# untitled.net
KiCad netlist of a schematic drawn in EAGLE
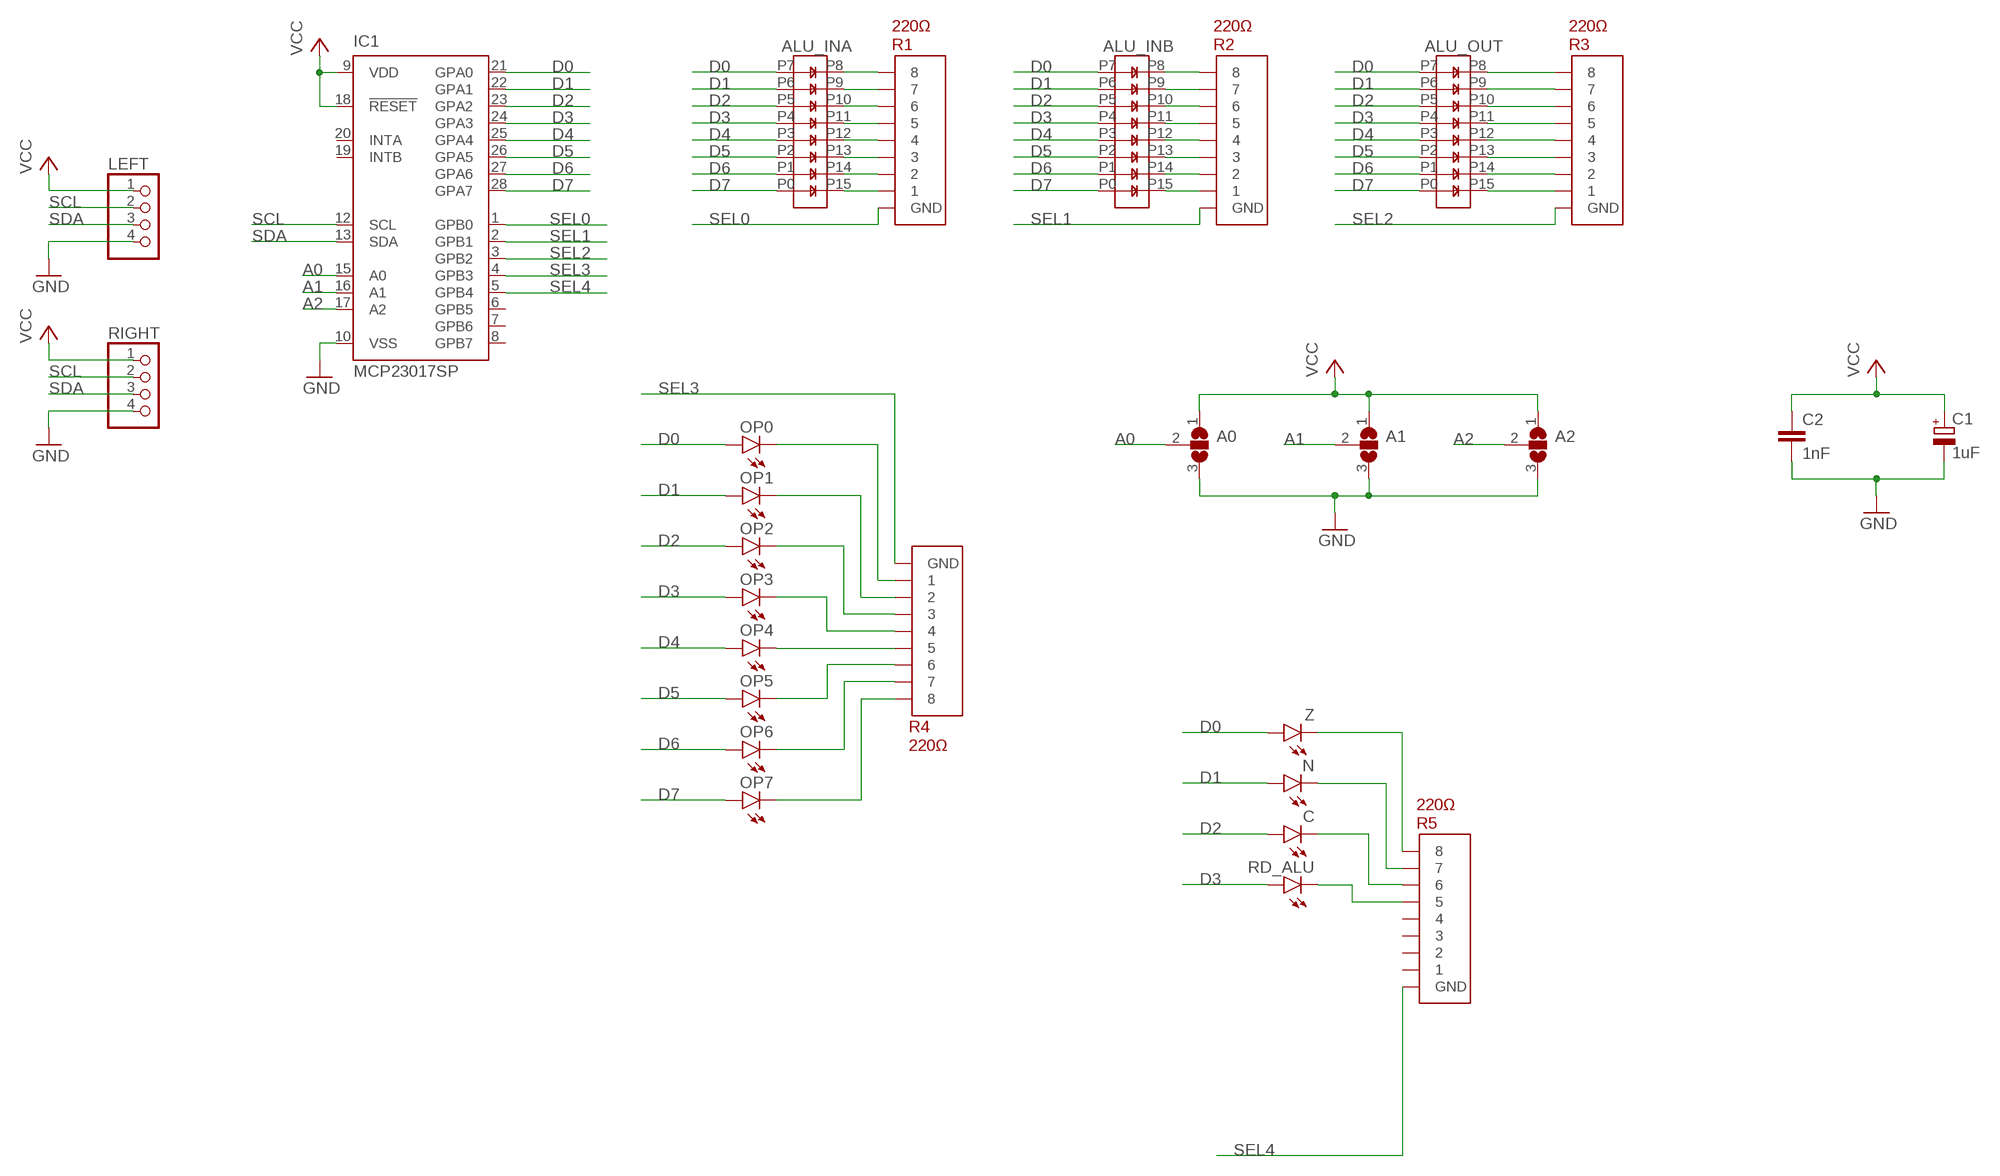
[diagram p0: schematic, sheet 1]

(export (version "E")
  (design (tool "Eeschema 10.0.6"))
  (components
    (comp (ref "A0")
      (value "SJ2W")
      (footprint "eagle-import:SJ_2")
      (libsource (lib "eagle-import") (part "SJ2W"))
    )
    (comp (ref "A1")
      (value "SJ2W")
      (footprint "eagle-import:SJ_2")
      (libsource (lib "eagle-import") (part "SJ2W"))
    )
    (comp (ref "A2")
      (value "SJ2W")
      (footprint "eagle-import:SJ_2")
      (libsource (lib "eagle-import") (part "SJ2W"))
    )
    (comp (ref "ALU_INA")
      (value "LB8")
      (footprint "eagle-import:LB8")
      (libsource (lib "eagle-import") (part "LB8"))
    )
    (comp (ref "ALU_INB")
      (value "LB8")
      (footprint "eagle-import:LB8")
      (libsource (lib "eagle-import") (part "LB8"))
    )
    (comp (ref "ALU_OUT")
      (value "LB8")
      (footprint "eagle-import:LB8")
      (libsource (lib "eagle-import") (part "LB8"))
    )
    (comp (ref "C")
      (value "LED3MM")
      (footprint "eagle-import:LED3MM")
      (libsource (lib "eagle-import") (part "LED3MM"))
    )
    (comp (ref "C1")
      (value "1uF")
      (footprint "eagle-import:E2,5-6")
      (libsource (lib "eagle-import") (part "CPOL-EUE2.5-6"))
    )
    (comp (ref "C2")
      (value "1nF")
      (footprint "eagle-import:C2.5-2")
      (libsource (lib "eagle-import") (part "C2.5/2"))
    )
    (comp (ref "IC1")
      (value "MCP23017SP")
      (footprint "eagle-import:DIL28-3")
      (fields (field (name "MF") "MICROCHIP") (field (name "MPN") "MCP23017-E/SP"))
      (libsource (lib "eagle-import") (part "MCP23017SP"))
    )
    (comp (ref "LEFT")
      (value "PINHD-1X4")
      (footprint "eagle-import:1X04")
      (libsource (lib "eagle-import") (part "PINHD-1X4"))
    )
    (comp (ref "N")
      (value "LED3MM")
      (footprint "eagle-import:LED3MM")
      (libsource (lib "eagle-import") (part "LED3MM"))
    )
    (comp (ref "OP0")
      (value "LED3MM")
      (footprint "eagle-import:LED3MM")
      (libsource (lib "eagle-import") (part "LED3MM"))
    )
    (comp (ref "OP1")
      (value "LED3MM")
      (footprint "eagle-import:LED3MM")
      (libsource (lib "eagle-import") (part "LED3MM"))
    )
    (comp (ref "OP2")
      (value "LED3MM")
      (footprint "eagle-import:LED3MM")
      (libsource (lib "eagle-import") (part "LED3MM"))
    )
    (comp (ref "OP3")
      (value "LED3MM")
      (footprint "eagle-import:LED3MM")
      (libsource (lib "eagle-import") (part "LED3MM"))
    )
    (comp (ref "OP4")
      (value "LED3MM")
      (footprint "eagle-import:LED3MM")
      (libsource (lib "eagle-import") (part "LED3MM"))
    )
    (comp (ref "OP5")
      (value "LED3MM")
      (footprint "eagle-import:LED3MM")
      (libsource (lib "eagle-import") (part "LED3MM"))
    )
    (comp (ref "OP6")
      (value "LED3MM")
      (footprint "eagle-import:LED3MM")
      (libsource (lib "eagle-import") (part "LED3MM"))
    )
    (comp (ref "OP7")
      (value "LED3MM")
      (footprint "eagle-import:LED3MM")
      (libsource (lib "eagle-import") (part "LED3MM"))
    )
    (comp (ref "R1")
      (value "220Ω")
      (footprint "eagle-import:R_ARRAY_8PIN")
      (libsource (lib "eagle-import") (part "R_ARRAY_8PIN"))
    )
    (comp (ref "R2")
      (value "220Ω")
      (footprint "eagle-import:R_ARRAY_8PIN")
      (libsource (lib "eagle-import") (part "R_ARRAY_8PIN"))
    )
    (comp (ref "R3")
      (value "220Ω")
      (footprint "eagle-import:R_ARRAY_8PIN")
      (libsource (lib "eagle-import") (part "R_ARRAY_8PIN"))
    )
    (comp (ref "R4")
      (value "220Ω")
      (footprint "eagle-import:R_ARRAY_8PIN")
      (libsource (lib "eagle-import") (part "R_ARRAY_8PIN"))
    )
    (comp (ref "R5")
      (value "220Ω")
      (footprint "eagle-import:R_ARRAY_8PIN")
      (libsource (lib "eagle-import") (part "R_ARRAY_8PIN"))
    )
    (comp (ref "RD_ALU")
      (value "LED3MM")
      (footprint "eagle-import:LED3MM")
      (libsource (lib "eagle-import") (part "LED3MM"))
    )
    (comp (ref "RIGHT")
      (value "PINHD-1X4")
      (footprint "eagle-import:1X04")
      (libsource (lib "eagle-import") (part "PINHD-1X4"))
    )
    (comp (ref "Z")
      (value "LED3MM")
      (footprint "eagle-import:LED3MM")
      (libsource (lib "eagle-import") (part "LED3MM"))
    )
  )
  (nets
    (net (code "1") (name "/A0") (class "Default")
      (node (ref "A0") (pin "2") (pinfunction "2_2") (pintype "passive"))
      (node (ref "IC1") (pin "15") (pinfunction "A0_15") (pintype "input"))
    )
    (net (code "2") (name "/A1") (class "Default")
      (node (ref "A1") (pin "2") (pinfunction "2_2") (pintype "passive"))
      (node (ref "IC1") (pin "16") (pinfunction "A1_16") (pintype "input"))
    )
    (net (code "3") (name "/A2") (class "Default")
      (node (ref "A2") (pin "2") (pinfunction "2_2") (pintype "passive"))
      (node (ref "IC1") (pin "17") (pinfunction "A2_17") (pintype "input"))
    )
    (net (code "4") (name "/D0") (class "Default")
      (node (ref "ALU_INA") (pin "P7") (pinfunction "P7_P7") (pintype "bidirectional"))
      (node (ref "ALU_INB") (pin "P7") (pinfunction "P7_P7") (pintype "bidirectional"))
      (node (ref "ALU_OUT") (pin "P7") (pinfunction "P7_P7") (pintype "bidirectional"))
      (node (ref "IC1") (pin "21") (pinfunction "GPA0_21") (pintype "bidirectional"))
      (node (ref "OP0") (pin "A") (pinfunction "A_A") (pintype "passive"))
      (node (ref "Z") (pin "A") (pinfunction "A_A") (pintype "passive"))
    )
    (net (code "5") (name "/D1") (class "Default")
      (node (ref "ALU_INA") (pin "P6") (pinfunction "P6_P6") (pintype "bidirectional"))
      (node (ref "ALU_INB") (pin "P6") (pinfunction "P6_P6") (pintype "bidirectional"))
      (node (ref "ALU_OUT") (pin "P6") (pinfunction "P6_P6") (pintype "bidirectional"))
      (node (ref "IC1") (pin "22") (pinfunction "GPA1_22") (pintype "bidirectional"))
      (node (ref "N") (pin "A") (pinfunction "A_A") (pintype "passive"))
      (node (ref "OP1") (pin "A") (pinfunction "A_A") (pintype "passive"))
    )
    (net (code "6") (name "/D2") (class "Default")
      (node (ref "ALU_INA") (pin "P5") (pinfunction "P5_P5") (pintype "bidirectional"))
      (node (ref "ALU_INB") (pin "P5") (pinfunction "P5_P5") (pintype "bidirectional"))
      (node (ref "ALU_OUT") (pin "P5") (pinfunction "P5_P5") (pintype "bidirectional"))
      (node (ref "C") (pin "A") (pinfunction "A_A") (pintype "passive"))
      (node (ref "IC1") (pin "23") (pinfunction "GPA2_23") (pintype "bidirectional"))
      (node (ref "OP2") (pin "A") (pinfunction "A_A") (pintype "passive"))
    )
    (net (code "7") (name "/D3") (class "Default")
      (node (ref "ALU_INA") (pin "P4") (pinfunction "P4_P4") (pintype "bidirectional"))
      (node (ref "ALU_INB") (pin "P4") (pinfunction "P4_P4") (pintype "bidirectional"))
      (node (ref "ALU_OUT") (pin "P4") (pinfunction "P4_P4") (pintype "bidirectional"))
      (node (ref "IC1") (pin "24") (pinfunction "GPA3_24") (pintype "bidirectional"))
      (node (ref "OP3") (pin "A") (pinfunction "A_A") (pintype "passive"))
      (node (ref "RD_ALU") (pin "A") (pinfunction "A_A") (pintype "passive"))
    )
    (net (code "8") (name "/D4") (class "Default")
      (node (ref "ALU_INA") (pin "P3") (pinfunction "P3_P3") (pintype "bidirectional"))
      (node (ref "ALU_INB") (pin "P3") (pinfunction "P3_P3") (pintype "bidirectional"))
      (node (ref "ALU_OUT") (pin "P3") (pinfunction "P3_P3") (pintype "bidirectional"))
      (node (ref "IC1") (pin "25") (pinfunction "GPA4_25") (pintype "bidirectional"))
      (node (ref "OP4") (pin "A") (pinfunction "A_A") (pintype "passive"))
    )
    (net (code "9") (name "/D5") (class "Default")
      (node (ref "ALU_INA") (pin "P2") (pinfunction "P2_P2") (pintype "bidirectional"))
      (node (ref "ALU_INB") (pin "P2") (pinfunction "P2_P2") (pintype "bidirectional"))
      (node (ref "ALU_OUT") (pin "P2") (pinfunction "P2_P2") (pintype "bidirectional"))
      (node (ref "IC1") (pin "26") (pinfunction "GPA5_26") (pintype "bidirectional"))
      (node (ref "OP5") (pin "A") (pinfunction "A_A") (pintype "passive"))
    )
    (net (code "10") (name "/D6") (class "Default")
      (node (ref "ALU_INA") (pin "P1") (pinfunction "P1_P1") (pintype "bidirectional"))
      (node (ref "ALU_INB") (pin "P1") (pinfunction "P1_P1") (pintype "bidirectional"))
      (node (ref "ALU_OUT") (pin "P1") (pinfunction "P1_P1") (pintype "bidirectional"))
      (node (ref "IC1") (pin "27") (pinfunction "GPA6_27") (pintype "bidirectional"))
      (node (ref "OP6") (pin "A") (pinfunction "A_A") (pintype "passive"))
    )
    (net (code "11") (name "/D7") (class "Default")
      (node (ref "ALU_INA") (pin "P0") (pinfunction "P0_P0") (pintype "bidirectional"))
      (node (ref "ALU_INB") (pin "P0") (pinfunction "P0_P0") (pintype "bidirectional"))
      (node (ref "ALU_OUT") (pin "P0") (pinfunction "P0_P0") (pintype "bidirectional"))
      (node (ref "IC1") (pin "28") (pinfunction "GPA7_28") (pintype "bidirectional"))
      (node (ref "OP7") (pin "A") (pinfunction "A_A") (pintype "passive"))
    )
    (net (code "12") (name "/SCL") (class "Default")
      (node (ref "IC1") (pin "12") (pinfunction "SCL_12") (pintype "input"))
      (node (ref "LEFT") (pin "2") (pinfunction "2_2") (pintype "passive"))
      (node (ref "RIGHT") (pin "2") (pinfunction "2_2") (pintype "passive"))
    )
    (net (code "13") (name "/SDA") (class "Default")
      (node (ref "IC1") (pin "13") (pinfunction "SDA_13") (pintype "bidirectional"))
      (node (ref "LEFT") (pin "3") (pinfunction "3_3") (pintype "passive"))
      (node (ref "RIGHT") (pin "3") (pinfunction "3_3") (pintype "passive"))
    )
    (net (code "14") (name "/SEL0") (class "Default")
      (node (ref "IC1") (pin "1") (pinfunction "GPB0_1") (pintype "bidirectional"))
      (node (ref "R1") (pin "GND") (pinfunction "GND_GND") (pintype "bidirectional"))
    )
    (net (code "15") (name "/SEL1") (class "Default")
      (node (ref "IC1") (pin "2") (pinfunction "GPB1_2") (pintype "bidirectional"))
      (node (ref "R2") (pin "GND") (pinfunction "GND_GND") (pintype "bidirectional"))
    )
    (net (code "16") (name "/SEL2") (class "Default")
      (node (ref "IC1") (pin "3") (pinfunction "GPB2_3") (pintype "bidirectional"))
      (node (ref "R3") (pin "GND") (pinfunction "GND_GND") (pintype "bidirectional"))
    )
    (net (code "17") (name "/SEL3") (class "Default")
      (node (ref "IC1") (pin "4") (pinfunction "GPB3_4") (pintype "bidirectional"))
      (node (ref "R4") (pin "GND") (pinfunction "GND_GND") (pintype "bidirectional"))
    )
    (net (code "18") (name "/SEL4") (class "Default")
      (node (ref "IC1") (pin "5") (pinfunction "GPB4_5") (pintype "bidirectional"))
      (node (ref "R5") (pin "GND") (pinfunction "GND_GND") (pintype "bidirectional"))
    )
    (net (code "19") (name "GND") (class "Default")
      (node (ref "A0") (pin "3") (pinfunction "3_3") (pintype "passive"))
      (node (ref "A1") (pin "3") (pinfunction "3_3") (pintype "passive"))
      (node (ref "A2") (pin "3") (pinfunction "3_3") (pintype "passive"))
      (node (ref "C1") (pin "-") (pinfunction "-_-") (pintype "passive"))
      (node (ref "C2") (pin "2") (pinfunction "2_2") (pintype "passive"))
      (node (ref "IC1") (pin "10") (pinfunction "VSS_10") (pintype "power_in"))
      (node (ref "LEFT") (pin "4") (pinfunction "4_4") (pintype "passive"))
      (node (ref "RIGHT") (pin "4") (pinfunction "4_4") (pintype "passive"))
    )
    (net (code "20") (name "Net-(ALU_INA-PadP8)") (class "Default")
      (node (ref "ALU_INA") (pin "P8") (pinfunction "P8_P8") (pintype "bidirectional"))
      (node (ref "R1") (pin "8") (pinfunction "8_8") (pintype "bidirectional"))
    )
    (net (code "21") (name "Net-(ALU_INA-PadP9)") (class "Default")
      (node (ref "ALU_INA") (pin "P9") (pinfunction "P9_P9") (pintype "bidirectional"))
      (node (ref "R1") (pin "7") (pinfunction "7_7") (pintype "bidirectional"))
    )
    (net (code "22") (name "Net-(ALU_INA-PadP10)") (class "Default")
      (node (ref "ALU_INA") (pin "P10") (pinfunction "P10_P10") (pintype "bidirectional"))
      (node (ref "R1") (pin "6") (pinfunction "6_6") (pintype "bidirectional"))
    )
    (net (code "23") (name "Net-(ALU_INA-PadP11)") (class "Default")
      (node (ref "ALU_INA") (pin "P11") (pinfunction "P11_P11") (pintype "bidirectional"))
      (node (ref "R1") (pin "5") (pinfunction "5_5") (pintype "bidirectional"))
    )
    (net (code "24") (name "Net-(ALU_INA-PadP12)") (class "Default")
      (node (ref "ALU_INA") (pin "P12") (pinfunction "P12_P12") (pintype "bidirectional"))
      (node (ref "R1") (pin "4") (pinfunction "4_4") (pintype "bidirectional"))
    )
    (net (code "25") (name "Net-(ALU_INA-PadP13)") (class "Default")
      (node (ref "ALU_INA") (pin "P13") (pinfunction "P13_P13") (pintype "bidirectional"))
      (node (ref "R1") (pin "3") (pinfunction "3_3") (pintype "bidirectional"))
    )
    (net (code "26") (name "Net-(ALU_INA-PadP14)") (class "Default")
      (node (ref "ALU_INA") (pin "P14") (pinfunction "P14_P14") (pintype "bidirectional"))
      (node (ref "R1") (pin "2") (pinfunction "2_2") (pintype "bidirectional"))
    )
    (net (code "27") (name "Net-(ALU_INA-PadP15)") (class "Default")
      (node (ref "ALU_INA") (pin "P15") (pinfunction "P15_P15") (pintype "bidirectional"))
      (node (ref "R1") (pin "1") (pinfunction "1_1") (pintype "bidirectional"))
    )
    (net (code "28") (name "Net-(ALU_INB-PadP8)") (class "Default")
      (node (ref "ALU_INB") (pin "P8") (pinfunction "P8_P8") (pintype "bidirectional"))
      (node (ref "R2") (pin "8") (pinfunction "8_8") (pintype "bidirectional"))
    )
    (net (code "29") (name "Net-(ALU_INB-PadP9)") (class "Default")
      (node (ref "ALU_INB") (pin "P9") (pinfunction "P9_P9") (pintype "bidirectional"))
      (node (ref "R2") (pin "7") (pinfunction "7_7") (pintype "bidirectional"))
    )
    (net (code "30") (name "Net-(ALU_INB-PadP10)") (class "Default")
      (node (ref "ALU_INB") (pin "P10") (pinfunction "P10_P10") (pintype "bidirectional"))
      (node (ref "R2") (pin "6") (pinfunction "6_6") (pintype "bidirectional"))
    )
    (net (code "31") (name "Net-(ALU_INB-PadP11)") (class "Default")
      (node (ref "ALU_INB") (pin "P11") (pinfunction "P11_P11") (pintype "bidirectional"))
      (node (ref "R2") (pin "5") (pinfunction "5_5") (pintype "bidirectional"))
    )
    (net (code "32") (name "Net-(ALU_INB-PadP12)") (class "Default")
      (node (ref "ALU_INB") (pin "P12") (pinfunction "P12_P12") (pintype "bidirectional"))
      (node (ref "R2") (pin "4") (pinfunction "4_4") (pintype "bidirectional"))
    )
    (net (code "33") (name "Net-(ALU_INB-PadP13)") (class "Default")
      (node (ref "ALU_INB") (pin "P13") (pinfunction "P13_P13") (pintype "bidirectional"))
      (node (ref "R2") (pin "3") (pinfunction "3_3") (pintype "bidirectional"))
    )
    (net (code "34") (name "Net-(ALU_INB-PadP14)") (class "Default")
      (node (ref "ALU_INB") (pin "P14") (pinfunction "P14_P14") (pintype "bidirectional"))
      (node (ref "R2") (pin "2") (pinfunction "2_2") (pintype "bidirectional"))
    )
    (net (code "35") (name "Net-(ALU_INB-PadP15)") (class "Default")
      (node (ref "ALU_INB") (pin "P15") (pinfunction "P15_P15") (pintype "bidirectional"))
      (node (ref "R2") (pin "1") (pinfunction "1_1") (pintype "bidirectional"))
    )
    (net (code "36") (name "Net-(ALU_OUT-PadP8)") (class "Default")
      (node (ref "ALU_OUT") (pin "P8") (pinfunction "P8_P8") (pintype "bidirectional"))
      (node (ref "R3") (pin "8") (pinfunction "8_8") (pintype "bidirectional"))
    )
    (net (code "37") (name "Net-(ALU_OUT-PadP9)") (class "Default")
      (node (ref "ALU_OUT") (pin "P9") (pinfunction "P9_P9") (pintype "bidirectional"))
      (node (ref "R3") (pin "7") (pinfunction "7_7") (pintype "bidirectional"))
    )
    (net (code "38") (name "Net-(ALU_OUT-PadP10)") (class "Default")
      (node (ref "ALU_OUT") (pin "P10") (pinfunction "P10_P10") (pintype "bidirectional"))
      (node (ref "R3") (pin "6") (pinfunction "6_6") (pintype "bidirectional"))
    )
    (net (code "39") (name "Net-(ALU_OUT-PadP11)") (class "Default")
      (node (ref "ALU_OUT") (pin "P11") (pinfunction "P11_P11") (pintype "bidirectional"))
      (node (ref "R3") (pin "5") (pinfunction "5_5") (pintype "bidirectional"))
    )
    (net (code "40") (name "Net-(ALU_OUT-PadP12)") (class "Default")
      (node (ref "ALU_OUT") (pin "P12") (pinfunction "P12_P12") (pintype "bidirectional"))
      (node (ref "R3") (pin "4") (pinfunction "4_4") (pintype "bidirectional"))
    )
    (net (code "41") (name "Net-(ALU_OUT-PadP13)") (class "Default")
      (node (ref "ALU_OUT") (pin "P13") (pinfunction "P13_P13") (pintype "bidirectional"))
      (node (ref "R3") (pin "3") (pinfunction "3_3") (pintype "bidirectional"))
    )
    (net (code "42") (name "Net-(ALU_OUT-PadP14)") (class "Default")
      (node (ref "ALU_OUT") (pin "P14") (pinfunction "P14_P14") (pintype "bidirectional"))
      (node (ref "R3") (pin "2") (pinfunction "2_2") (pintype "bidirectional"))
    )
    (net (code "43") (name "Net-(ALU_OUT-PadP15)") (class "Default")
      (node (ref "ALU_OUT") (pin "P15") (pinfunction "P15_P15") (pintype "bidirectional"))
      (node (ref "R3") (pin "1") (pinfunction "1_1") (pintype "bidirectional"))
    )
    (net (code "44") (name "Net-(C-C)") (class "Default")
      (node (ref "C") (pin "K") (pinfunction "C_K") (pintype "passive"))
      (node (ref "R5") (pin "6") (pinfunction "6_6") (pintype "bidirectional"))
    )
    (net (code "45") (name "Net-(N-C)") (class "Default")
      (node (ref "N") (pin "K") (pinfunction "C_K") (pintype "passive"))
      (node (ref "R5") (pin "7") (pinfunction "7_7") (pintype "bidirectional"))
    )
    (net (code "46") (name "Net-(OP0-C)") (class "Default")
      (node (ref "OP0") (pin "K") (pinfunction "C_K") (pintype "passive"))
      (node (ref "R4") (pin "1") (pinfunction "1_1") (pintype "bidirectional"))
    )
    (net (code "47") (name "Net-(OP1-C)") (class "Default")
      (node (ref "OP1") (pin "K") (pinfunction "C_K") (pintype "passive"))
      (node (ref "R4") (pin "2") (pinfunction "2_2") (pintype "bidirectional"))
    )
    (net (code "48") (name "Net-(OP2-C)") (class "Default")
      (node (ref "OP2") (pin "K") (pinfunction "C_K") (pintype "passive"))
      (node (ref "R4") (pin "3") (pinfunction "3_3") (pintype "bidirectional"))
    )
    (net (code "49") (name "Net-(OP3-C)") (class "Default")
      (node (ref "OP3") (pin "K") (pinfunction "C_K") (pintype "passive"))
      (node (ref "R4") (pin "4") (pinfunction "4_4") (pintype "bidirectional"))
    )
    (net (code "50") (name "Net-(OP4-C)") (class "Default")
      (node (ref "OP4") (pin "K") (pinfunction "C_K") (pintype "passive"))
      (node (ref "R4") (pin "5") (pinfunction "5_5") (pintype "bidirectional"))
    )
    (net (code "51") (name "Net-(OP5-C)") (class "Default")
      (node (ref "OP5") (pin "K") (pinfunction "C_K") (pintype "passive"))
      (node (ref "R4") (pin "6") (pinfunction "6_6") (pintype "bidirectional"))
    )
    (net (code "52") (name "Net-(OP6-C)") (class "Default")
      (node (ref "OP6") (pin "K") (pinfunction "C_K") (pintype "passive"))
      (node (ref "R4") (pin "7") (pinfunction "7_7") (pintype "bidirectional"))
    )
    (net (code "53") (name "Net-(OP7-C)") (class "Default")
      (node (ref "OP7") (pin "K") (pinfunction "C_K") (pintype "passive"))
      (node (ref "R4") (pin "8") (pinfunction "8_8") (pintype "bidirectional"))
    )
    (net (code "54") (name "Net-(RD_ALU-C)") (class "Default")
      (node (ref "R5") (pin "5") (pinfunction "5_5") (pintype "bidirectional"))
      (node (ref "RD_ALU") (pin "K") (pinfunction "C_K") (pintype "passive"))
    )
    (net (code "55") (name "Net-(Z-C)") (class "Default")
      (node (ref "R5") (pin "8") (pinfunction "8_8") (pintype "bidirectional"))
      (node (ref "Z") (pin "K") (pinfunction "C_K") (pintype "passive"))
    )
    (net (code "56") (name "VCC") (class "Default")
      (node (ref "A0") (pin "1") (pinfunction "1_1") (pintype "passive"))
      (node (ref "A1") (pin "1") (pinfunction "1_1") (pintype "passive"))
      (node (ref "A2") (pin "1") (pinfunction "1_1") (pintype "passive"))
      (node (ref "C1") (pin "+") (pinfunction "+_+") (pintype "passive"))
      (node (ref "C2") (pin "1") (pinfunction "1_1") (pintype "passive"))
      (node (ref "IC1") (pin "18") (pinfunction "~{RESET}_18") (pintype "input"))
      (node (ref "IC1") (pin "9") (pinfunction "VDD_9") (pintype "power_in"))
      (node (ref "LEFT") (pin "1") (pinfunction "1_1") (pintype "passive"))
      (node (ref "RIGHT") (pin "1") (pinfunction "1_1") (pintype "passive"))
    )
    (net (code "57") (name "unconnected-(IC1-GPB5-Pad6)") (class "Default")
      (node (ref "IC1") (pin "6") (pinfunction "GPB5_6") (pintype "bidirectional"))
    )
    (net (code "58") (name "unconnected-(IC1-GPB6-Pad7)") (class "Default")
      (node (ref "IC1") (pin "7") (pinfunction "GPB6_7") (pintype "bidirectional"))
    )
    (net (code "59") (name "unconnected-(IC1-GPB7-Pad8)") (class "Default")
      (node (ref "IC1") (pin "8") (pinfunction "GPB7_8") (pintype "bidirectional"))
    )
    (net (code "60") (name "unconnected-(IC1-INTA-Pad20)") (class "Default")
      (node (ref "IC1") (pin "20") (pinfunction "INTA_20") (pintype "output"))
    )
    (net (code "61") (name "unconnected-(IC1-INTB-Pad19)") (class "Default")
      (node (ref "IC1") (pin "19") (pinfunction "INTB_19") (pintype "output"))
    )
    (net (code "62") (name "unconnected-(R5-Pad1)") (class "Default")
      (node (ref "R5") (pin "1") (pinfunction "1_1") (pintype "bidirectional"))
    )
    (net (code "63") (name "unconnected-(R5-Pad2)") (class "Default")
      (node (ref "R5") (pin "2") (pinfunction "2_2") (pintype "bidirectional"))
    )
    (net (code "64") (name "unconnected-(R5-Pad3)") (class "Default")
      (node (ref "R5") (pin "3") (pinfunction "3_3") (pintype "bidirectional"))
    )
    (net (code "65") (name "unconnected-(R5-Pad4)") (class "Default")
      (node (ref "R5") (pin "4") (pinfunction "4_4") (pintype "bidirectional"))
    )
  )
)
